# cyc_v_som_B.net
KiCad netlist of a schematic drawn in Altium Designer
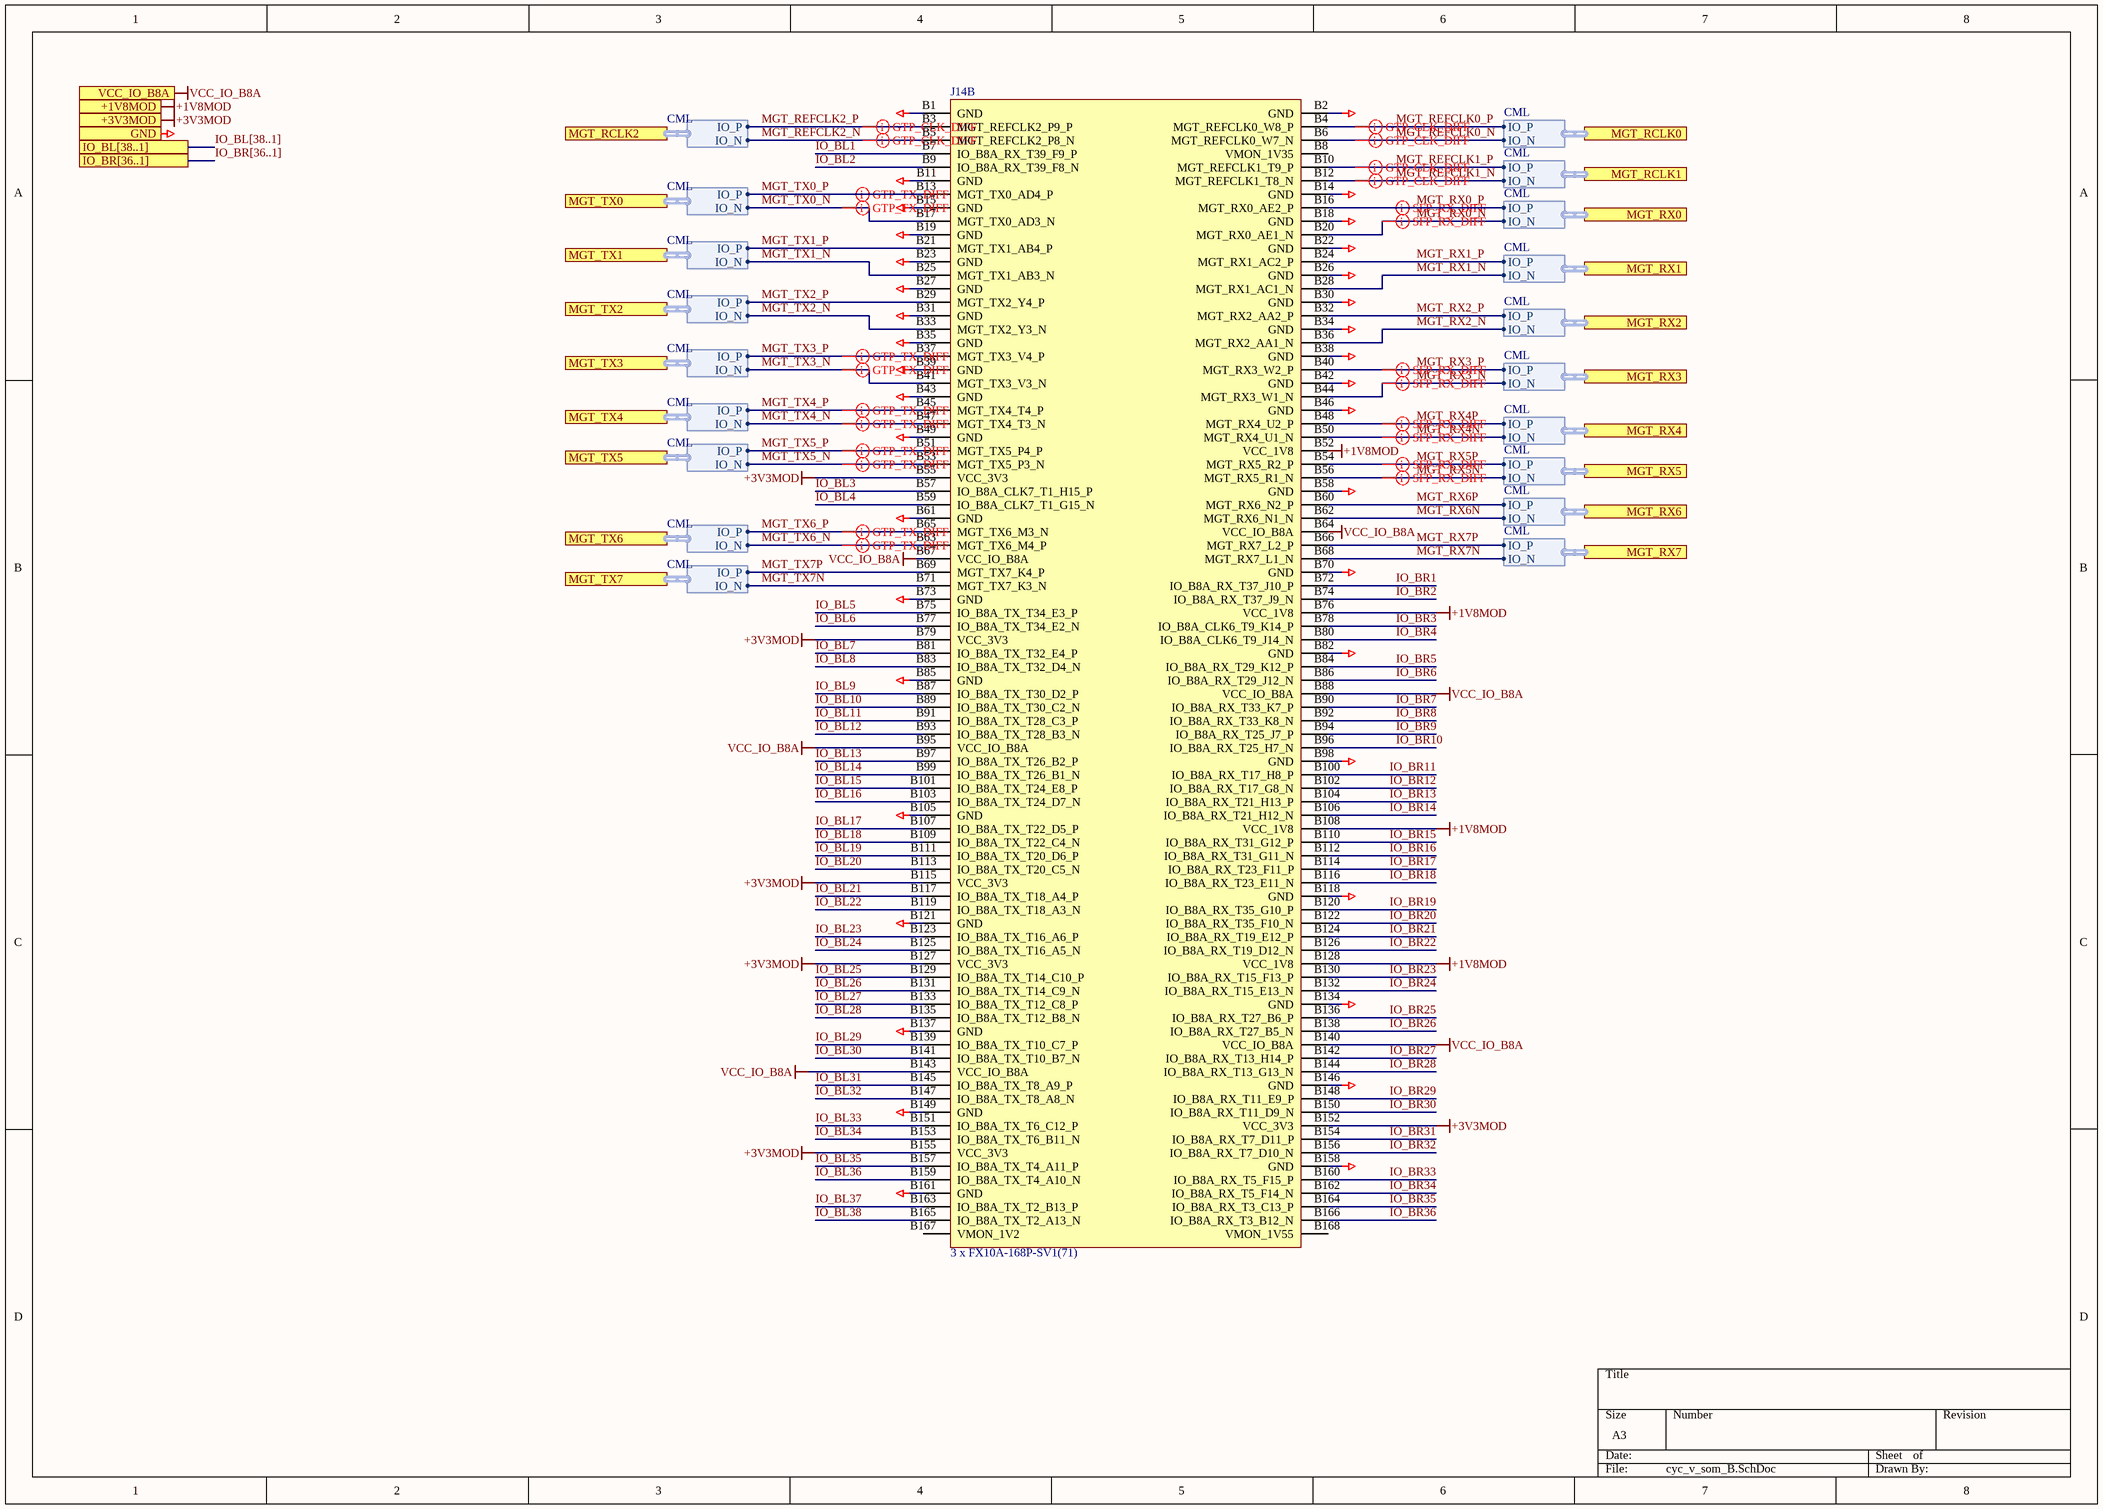
[diagram p0: cyc_v_som_B.SchDoc]

(export (version "E")
  (design (tool "Eeschema 10.0.6"))
  (components
    (comp (ref "J14")
      (value "3 x FX10A-168P-SV1(71)")
      (footprint "Mercury_SA2p")
      (libsource (lib "ConLib") (part "FX10A-168P-SV_ME-SA2+"))
    )
  )
  (nets
    (net (code "2") (name "+1V8MOD") (class "Default")
      (node (ref "J14") (pin "B108") (pinfunction "VCC_1V8_B108") (pintype "passive"))
      (node (ref "J14") (pin "B128") (pinfunction "VCC_1V8_B128") (pintype "passive"))
      (node (ref "J14") (pin "B52") (pinfunction "VCC_1V8_B52") (pintype "passive"))
      (node (ref "J14") (pin "B76") (pinfunction "VCC_1V8_B76") (pintype "passive"))
    )
    (net (code "3") (name "+3V3MOD") (class "Default")
      (node (ref "J14") (pin "B115") (pinfunction "VCC_3V3_B115") (pintype "passive"))
      (node (ref "J14") (pin "B127") (pinfunction "VCC_3V3_B127") (pintype "passive"))
      (node (ref "J14") (pin "B152") (pinfunction "VCC_3V3_B152") (pintype "passive"))
      (node (ref "J14") (pin "B155") (pinfunction "VCC_3V3_B155") (pintype "passive"))
      (node (ref "J14") (pin "B55") (pinfunction "VCC_3V3_B55") (pintype "passive"))
      (node (ref "J14") (pin "B79") (pinfunction "VCC_3V3_B79") (pintype "passive"))
    )
    (net (code "4") (name "/IO_BL1") (class "Default")
      (node (ref "J14") (pin "B7") (pinfunction "IO_B8A_RX_T39_F9_P_B7") (pintype "passive"))
    )
    (net (code "5") (name "/IO_BL2") (class "Default")
      (node (ref "J14") (pin "B9") (pinfunction "IO_B8A_RX_T39_F8_N_B9") (pintype "passive"))
    )
    (net (code "6") (name "/IO_BL3") (class "Default")
      (node (ref "J14") (pin "B57") (pinfunction "IO_B8A_CLK7_T1_H15_P_B57") (pintype "passive"))
    )
    (net (code "7") (name "/IO_BL4") (class "Default")
      (node (ref "J14") (pin "B59") (pinfunction "IO_B8A_CLK7_T1_G15_N_B59") (pintype "passive"))
    )
    (net (code "8") (name "/IO_BL5") (class "Default")
      (node (ref "J14") (pin "B75") (pinfunction "IO_B8A_TX_T34_E3_P_B75") (pintype "passive"))
    )
    (net (code "9") (name "/IO_BL6") (class "Default")
      (node (ref "J14") (pin "B77") (pinfunction "IO_B8A_TX_T34_E2_N_B77") (pintype "passive"))
    )
    (net (code "10") (name "/IO_BL7") (class "Default")
      (node (ref "J14") (pin "B81") (pinfunction "IO_B8A_TX_T32_E4_P_B81") (pintype "passive"))
    )
    (net (code "11") (name "/IO_BL8") (class "Default")
      (node (ref "J14") (pin "B83") (pinfunction "IO_B8A_TX_T32_D4_N_B83") (pintype "passive"))
    )
    (net (code "12") (name "/IO_BL9") (class "Default")
      (node (ref "J14") (pin "B87") (pinfunction "IO_B8A_TX_T30_D2_P_B87") (pintype "passive"))
    )
    (net (code "13") (name "/IO_BL10") (class "Default")
      (node (ref "J14") (pin "B89") (pinfunction "IO_B8A_TX_T30_C2_N_B89") (pintype "passive"))
    )
    (net (code "14") (name "/IO_BL11") (class "Default")
      (node (ref "J14") (pin "B91") (pinfunction "IO_B8A_TX_T28_C3_P_B91") (pintype "passive"))
    )
    (net (code "15") (name "/IO_BL12") (class "Default")
      (node (ref "J14") (pin "B93") (pinfunction "IO_B8A_TX_T28_B3_N_B93") (pintype "passive"))
    )
    (net (code "16") (name "/IO_BL13") (class "Default")
      (node (ref "J14") (pin "B97") (pinfunction "IO_B8A_TX_T26_B2_P_B97") (pintype "passive"))
    )
    (net (code "17") (name "/IO_BL14") (class "Default")
      (node (ref "J14") (pin "B99") (pinfunction "IO_B8A_TX_T26_B1_N_B99") (pintype "passive"))
    )
    (net (code "18") (name "/IO_BL15") (class "Default")
      (node (ref "J14") (pin "B101") (pinfunction "IO_B8A_TX_T24_E8_P_B101") (pintype "passive"))
    )
    (net (code "19") (name "/IO_BL16") (class "Default")
      (node (ref "J14") (pin "B103") (pinfunction "IO_B8A_TX_T24_D7_N_B103") (pintype "passive"))
    )
    (net (code "20") (name "/IO_BL17") (class "Default")
      (node (ref "J14") (pin "B107") (pinfunction "IO_B8A_TX_T22_D5_P_B107") (pintype "passive"))
    )
    (net (code "21") (name "/IO_BL18") (class "Default")
      (node (ref "J14") (pin "B109") (pinfunction "IO_B8A_TX_T22_C4_N_B109") (pintype "passive"))
    )
    (net (code "22") (name "/IO_BL19") (class "Default")
      (node (ref "J14") (pin "B111") (pinfunction "IO_B8A_TX_T20_D6_P_B111") (pintype "passive"))
    )
    (net (code "23") (name "/IO_BL20") (class "Default")
      (node (ref "J14") (pin "B113") (pinfunction "IO_B8A_TX_T20_C5_N_B113") (pintype "passive"))
    )
    (net (code "24") (name "/IO_BL21") (class "Default")
      (node (ref "J14") (pin "B117") (pinfunction "IO_B8A_TX_T18_A4_P_B117") (pintype "passive"))
    )
    (net (code "25") (name "/IO_BL22") (class "Default")
      (node (ref "J14") (pin "B119") (pinfunction "IO_B8A_TX_T18_A3_N_B119") (pintype "passive"))
    )
    (net (code "26") (name "/IO_BL23") (class "Default")
      (node (ref "J14") (pin "B123") (pinfunction "IO_B8A_TX_T16_A6_P_B123") (pintype "passive"))
    )
    (net (code "27") (name "/IO_BL24") (class "Default")
      (node (ref "J14") (pin "B125") (pinfunction "IO_B8A_TX_T16_A5_N_B125") (pintype "passive"))
    )
    (net (code "28") (name "/IO_BL25") (class "Default")
      (node (ref "J14") (pin "B129") (pinfunction "IO_B8A_TX_T14_C10_P_B129") (pintype "passive"))
    )
    (net (code "29") (name "/IO_BL26") (class "Default")
      (node (ref "J14") (pin "B131") (pinfunction "IO_B8A_TX_T14_C9_N_B131") (pintype "passive"))
    )
    (net (code "30") (name "/IO_BL27") (class "Default")
      (node (ref "J14") (pin "B133") (pinfunction "IO_B8A_TX_T12_C8_P_B133") (pintype "passive"))
    )
    (net (code "31") (name "/IO_BL28") (class "Default")
      (node (ref "J14") (pin "B135") (pinfunction "IO_B8A_TX_T12_B8_N_B135") (pintype "passive"))
    )
    (net (code "32") (name "/IO_BL29") (class "Default")
      (node (ref "J14") (pin "B139") (pinfunction "IO_B8A_TX_T10_C7_P_B139") (pintype "passive"))
    )
    (net (code "33") (name "/IO_BL30") (class "Default")
      (node (ref "J14") (pin "B141") (pinfunction "IO_B8A_TX_T10_B7_N_B141") (pintype "passive"))
    )
    (net (code "34") (name "/IO_BL31") (class "Default")
      (node (ref "J14") (pin "B145") (pinfunction "IO_B8A_TX_T8_A9_P_B145") (pintype "passive"))
    )
    (net (code "35") (name "/IO_BL32") (class "Default")
      (node (ref "J14") (pin "B147") (pinfunction "IO_B8A_TX_T8_A8_N_B147") (pintype "passive"))
    )
    (net (code "36") (name "/IO_BL33") (class "Default")
      (node (ref "J14") (pin "B151") (pinfunction "IO_B8A_TX_T6_C12_P_B151") (pintype "passive"))
    )
    (net (code "37") (name "/IO_BL34") (class "Default")
      (node (ref "J14") (pin "B153") (pinfunction "IO_B8A_TX_T6_B11_N_B153") (pintype "passive"))
    )
    (net (code "38") (name "/IO_BL35") (class "Default")
      (node (ref "J14") (pin "B157") (pinfunction "IO_B8A_TX_T4_A11_P_B157") (pintype "passive"))
    )
    (net (code "39") (name "/IO_BL36") (class "Default")
      (node (ref "J14") (pin "B159") (pinfunction "IO_B8A_TX_T4_A10_N_B159") (pintype "passive"))
    )
    (net (code "40") (name "/IO_BL37") (class "Default")
      (node (ref "J14") (pin "B163") (pinfunction "IO_B8A_TX_T2_B13_P_B163") (pintype "passive"))
    )
    (net (code "41") (name "/IO_BL38") (class "Default")
      (node (ref "J14") (pin "B165") (pinfunction "IO_B8A_TX_T2_A13_N_B165") (pintype "passive"))
    )
    (net (code "43") (name "/IO_BR1") (class "Default")
      (node (ref "J14") (pin "B72") (pinfunction "IO_B8A_RX_T37_J10_P_B72") (pintype "passive"))
    )
    (net (code "44") (name "/IO_BR2") (class "Default")
      (node (ref "J14") (pin "B74") (pinfunction "IO_B8A_RX_T37_J9_N_B74") (pintype "passive"))
    )
    (net (code "45") (name "/IO_BR3") (class "Default")
      (node (ref "J14") (pin "B78") (pinfunction "IO_B8A_CLK6_T9_K14_P_B78") (pintype "passive"))
    )
    (net (code "46") (name "/IO_BR4") (class "Default")
      (node (ref "J14") (pin "B80") (pinfunction "IO_B8A_CLK6_T9_J14_N_B80") (pintype "passive"))
    )
    (net (code "47") (name "/IO_BR5") (class "Default")
      (node (ref "J14") (pin "B84") (pinfunction "IO_B8A_RX_T29_K12_P_B84") (pintype "passive"))
    )
    (net (code "48") (name "/IO_BR6") (class "Default")
      (node (ref "J14") (pin "B86") (pinfunction "IO_B8A_RX_T29_J12_N_B86") (pintype "passive"))
    )
    (net (code "49") (name "/IO_BR7") (class "Default")
      (node (ref "J14") (pin "B90") (pinfunction "IO_B8A_RX_T33_K7_P_B90") (pintype "passive"))
    )
    (net (code "50") (name "/IO_BR8") (class "Default")
      (node (ref "J14") (pin "B92") (pinfunction "IO_B8A_RX_T33_K8_N_B92") (pintype "passive"))
    )
    (net (code "51") (name "/IO_BR9") (class "Default")
      (node (ref "J14") (pin "B94") (pinfunction "IO_B8A_RX_T25_J7_P_B94") (pintype "passive"))
    )
    (net (code "52") (name "/IO_BR10") (class "Default")
      (node (ref "J14") (pin "B96") (pinfunction "IO_B8A_RX_T25_H7_N_B96") (pintype "passive"))
    )
    (net (code "53") (name "/IO_BR11") (class "Default")
      (node (ref "J14") (pin "B100") (pinfunction "IO_B8A_RX_T17_H8_P_B100") (pintype "passive"))
    )
    (net (code "54") (name "/IO_BR12") (class "Default")
      (node (ref "J14") (pin "B102") (pinfunction "IO_B8A_RX_T17_G8_N_B102") (pintype "passive"))
    )
    (net (code "55") (name "/IO_BR13") (class "Default")
      (node (ref "J14") (pin "B104") (pinfunction "IO_B8A_RX_T21_H13_P_B104") (pintype "passive"))
    )
    (net (code "56") (name "/IO_BR14") (class "Default")
      (node (ref "J14") (pin "B106") (pinfunction "IO_B8A_RX_T21_H12_N_B106") (pintype "passive"))
    )
    (net (code "57") (name "/IO_BR15") (class "Default")
      (node (ref "J14") (pin "B110") (pinfunction "IO_B8A_RX_T31_G12_P_B110") (pintype "passive"))
    )
    (net (code "58") (name "/IO_BR16") (class "Default")
      (node (ref "J14") (pin "B112") (pinfunction "IO_B8A_RX_T31_G11_N_B112") (pintype "passive"))
    )
    (net (code "59") (name "/IO_BR17") (class "Default")
      (node (ref "J14") (pin "B114") (pinfunction "IO_B8A_RX_T23_F11_P_B114") (pintype "passive"))
    )
    (net (code "60") (name "/IO_BR18") (class "Default")
      (node (ref "J14") (pin "B116") (pinfunction "IO_B8A_RX_T23_E11_N_B116") (pintype "passive"))
    )
    (net (code "61") (name "/IO_BR19") (class "Default")
      (node (ref "J14") (pin "B120") (pinfunction "IO_B8A_RX_T35_G10_P_B120") (pintype "passive"))
    )
    (net (code "62") (name "/IO_BR20") (class "Default")
      (node (ref "J14") (pin "B122") (pinfunction "IO_B8A_RX_T35_F10_N_B122") (pintype "passive"))
    )
    (net (code "63") (name "/IO_BR21") (class "Default")
      (node (ref "J14") (pin "B124") (pinfunction "IO_B8A_RX_T19_E12_P_B124") (pintype "passive"))
    )
    (net (code "64") (name "/IO_BR22") (class "Default")
      (node (ref "J14") (pin "B126") (pinfunction "IO_B8A_RX_T19_D12_N_B126") (pintype "passive"))
    )
    (net (code "65") (name "/IO_BR23") (class "Default")
      (node (ref "J14") (pin "B130") (pinfunction "IO_B8A_RX_T15_F13_P_B130") (pintype "passive"))
    )
    (net (code "66") (name "/IO_BR24") (class "Default")
      (node (ref "J14") (pin "B132") (pinfunction "IO_B8A_RX_T15_E13_N_B132") (pintype "passive"))
    )
    (net (code "67") (name "/IO_BR25") (class "Default")
      (node (ref "J14") (pin "B136") (pinfunction "IO_B8A_RX_T27_B6_P_B136") (pintype "passive"))
    )
    (net (code "68") (name "/IO_BR26") (class "Default")
      (node (ref "J14") (pin "B138") (pinfunction "IO_B8A_RX_T27_B5_N_B138") (pintype "passive"))
    )
    (net (code "69") (name "/IO_BR27") (class "Default")
      (node (ref "J14") (pin "B142") (pinfunction "IO_B8A_RX_T13_H14_P_B142") (pintype "passive"))
    )
    (net (code "70") (name "/IO_BR28") (class "Default")
      (node (ref "J14") (pin "B144") (pinfunction "IO_B8A_RX_T13_G13_N_B144") (pintype "passive"))
    )
    (net (code "71") (name "/IO_BR29") (class "Default")
      (node (ref "J14") (pin "B148") (pinfunction "IO_B8A_RX_T11_E9_P_B148") (pintype "passive"))
    )
    (net (code "72") (name "/IO_BR30") (class "Default")
      (node (ref "J14") (pin "B150") (pinfunction "IO_B8A_RX_T11_D9_N_B150") (pintype "passive"))
    )
    (net (code "73") (name "/IO_BR31") (class "Default")
      (node (ref "J14") (pin "B154") (pinfunction "IO_B8A_RX_T7_D11_P_B154") (pintype "passive"))
    )
    (net (code "74") (name "/IO_BR32") (class "Default")
      (node (ref "J14") (pin "B156") (pinfunction "IO_B8A_RX_T7_D10_N_B156") (pintype "passive"))
    )
    (net (code "75") (name "/IO_BR33") (class "Default")
      (node (ref "J14") (pin "B160") (pinfunction "IO_B8A_RX_T5_F15_P_B160") (pintype "passive"))
    )
    (net (code "76") (name "/IO_BR34") (class "Default")
      (node (ref "J14") (pin "B162") (pinfunction "IO_B8A_RX_T5_F14_N_B162") (pintype "passive"))
    )
    (net (code "77") (name "/IO_BR35") (class "Default")
      (node (ref "J14") (pin "B164") (pinfunction "IO_B8A_RX_T3_C13_P_B164") (pintype "passive"))
    )
    (net (code "78") (name "/IO_BR36") (class "Default")
      (node (ref "J14") (pin "B166") (pinfunction "IO_B8A_RX_T3_B12_N_B166") (pintype "passive"))
    )
    (net (code "80") (name "/MGT_REFCLK0_N") (class "Default")
      (node (ref "J14") (pin "B6") (pinfunction "MGT_REFCLK0_W7_N_B6") (pintype "passive"))
    )
    (net (code "81") (name "/MGT_REFCLK0_P") (class "Default")
      (node (ref "J14") (pin "B4") (pinfunction "MGT_REFCLK0_W8_P_B4") (pintype "passive"))
    )
    (net (code "82") (name "/MGT_REFCLK1_N") (class "Default")
      (node (ref "J14") (pin "B12") (pinfunction "MGT_REFCLK1_T8_N_B12") (pintype "passive"))
    )
    (net (code "83") (name "/MGT_REFCLK1_P") (class "Default")
      (node (ref "J14") (pin "B10") (pinfunction "MGT_REFCLK1_T9_P_B10") (pintype "passive"))
    )
    (net (code "84") (name "/MGT_REFCLK2_N") (class "Default")
      (node (ref "J14") (pin "B5") (pinfunction "MGT_REFCLK2_P8_N_B5") (pintype "passive"))
    )
    (net (code "85") (name "/MGT_REFCLK2_P") (class "Default")
      (node (ref "J14") (pin "B3") (pinfunction "MGT_REFCLK2_P9_P_B3") (pintype "passive"))
    )
    (net (code "86") (name "/MGT_RX0_N") (class "Default")
      (node (ref "J14") (pin "B20") (pinfunction "MGT_RX0_AE1_N_B20") (pintype "passive"))
    )
    (net (code "87") (name "/MGT_RX0_P") (class "Default")
      (node (ref "J14") (pin "B16") (pinfunction "MGT_RX0_AE2_P_B16") (pintype "passive"))
    )
    (net (code "88") (name "/MGT_RX1_N") (class "Default")
      (node (ref "J14") (pin "B28") (pinfunction "MGT_RX1_AC1_N_B28") (pintype "passive"))
    )
    (net (code "89") (name "/MGT_RX1_P") (class "Default")
      (node (ref "J14") (pin "B24") (pinfunction "MGT_RX1_AC2_P_B24") (pintype "passive"))
    )
    (net (code "90") (name "/MGT_RX2_N") (class "Default")
      (node (ref "J14") (pin "B36") (pinfunction "MGT_RX2_AA1_N_B36") (pintype "passive"))
    )
    (net (code "91") (name "/MGT_RX2_P") (class "Default")
      (node (ref "J14") (pin "B32") (pinfunction "MGT_RX2_AA2_P_B32") (pintype "passive"))
    )
    (net (code "92") (name "/MGT_RX3_N") (class "Default")
      (node (ref "J14") (pin "B44") (pinfunction "MGT_RX3_W1_N_B44") (pintype "passive"))
    )
    (net (code "93") (name "/MGT_RX3_P") (class "Default")
      (node (ref "J14") (pin "B40") (pinfunction "MGT_RX3_W2_P_B40") (pintype "passive"))
    )
    (net (code "94") (name "/MGT_RX4N") (class "Default")
      (node (ref "J14") (pin "B50") (pinfunction "MGT_RX4_U1_N_B50") (pintype "passive"))
    )
    (net (code "95") (name "/MGT_RX4P") (class "Default")
      (node (ref "J14") (pin "B48") (pinfunction "MGT_RX4_U2_P_B48") (pintype "passive"))
    )
    (net (code "96") (name "/MGT_RX5N") (class "Default")
      (node (ref "J14") (pin "B56") (pinfunction "MGT_RX5_R1_N_B56") (pintype "passive"))
    )
    (net (code "97") (name "/MGT_RX5P") (class "Default")
      (node (ref "J14") (pin "B54") (pinfunction "MGT_RX5_R2_P_B54") (pintype "passive"))
    )
    (net (code "98") (name "/MGT_RX6N") (class "Default")
      (node (ref "J14") (pin "B62") (pinfunction "MGT_RX6_N1_N_B62") (pintype "passive"))
    )
    (net (code "99") (name "/MGT_RX6P") (class "Default")
      (node (ref "J14") (pin "B60") (pinfunction "MGT_RX6_N2_P_B60") (pintype "passive"))
    )
    (net (code "100") (name "/MGT_RX7N") (class "Default")
      (node (ref "J14") (pin "B68") (pinfunction "MGT_RX7_L1_N_B68") (pintype "passive"))
    )
    (net (code "101") (name "/MGT_RX7P") (class "Default")
      (node (ref "J14") (pin "B66") (pinfunction "MGT_RX7_L2_P_B66") (pintype "passive"))
    )
    (net (code "102") (name "/MGT_TX0_N") (class "Default")
      (node (ref "J14") (pin "B17") (pinfunction "MGT_TX0_AD3_N_B17") (pintype "passive"))
    )
    (net (code "103") (name "/MGT_TX0_P") (class "Default")
      (node (ref "J14") (pin "B13") (pinfunction "MGT_TX0_AD4_P_B13") (pintype "passive"))
    )
    (net (code "104") (name "/MGT_TX1_N") (class "Default")
      (node (ref "J14") (pin "B25") (pinfunction "MGT_TX1_AB3_N_B25") (pintype "passive"))
    )
    (net (code "105") (name "/MGT_TX1_P") (class "Default")
      (node (ref "J14") (pin "B21") (pinfunction "MGT_TX1_AB4_P_B21") (pintype "passive"))
    )
    (net (code "106") (name "/MGT_TX2_N") (class "Default")
      (node (ref "J14") (pin "B33") (pinfunction "MGT_TX2_Y3_N_B33") (pintype "passive"))
    )
    (net (code "107") (name "/MGT_TX2_P") (class "Default")
      (node (ref "J14") (pin "B29") (pinfunction "MGT_TX2_Y4_P_B29") (pintype "passive"))
    )
    (net (code "108") (name "/MGT_TX3_N") (class "Default")
      (node (ref "J14") (pin "B41") (pinfunction "MGT_TX3_V3_N_B41") (pintype "passive"))
    )
    (net (code "109") (name "/MGT_TX3_P") (class "Default")
      (node (ref "J14") (pin "B37") (pinfunction "MGT_TX3_V4_P_B37") (pintype "passive"))
    )
    (net (code "110") (name "/MGT_TX4_N") (class "Default")
      (node (ref "J14") (pin "B47") (pinfunction "MGT_TX4_T3_N_B47") (pintype "passive"))
    )
    (net (code "111") (name "/MGT_TX4_P") (class "Default")
      (node (ref "J14") (pin "B45") (pinfunction "MGT_TX4_T4_P_B45") (pintype "passive"))
    )
    (net (code "112") (name "/MGT_TX5_N") (class "Default")
      (node (ref "J14") (pin "B53") (pinfunction "MGT_TX5_P3_N_B53") (pintype "passive"))
    )
    (net (code "113") (name "/MGT_TX5_P") (class "Default")
      (node (ref "J14") (pin "B51") (pinfunction "MGT_TX5_P4_P_B51") (pintype "passive"))
    )
    (net (code "114") (name "/MGT_TX6_N") (class "Default")
      (node (ref "J14") (pin "B63") (pinfunction "MGT_TX6_M4_P_B63") (pintype "passive"))
    )
    (net (code "115") (name "/MGT_TX6_P") (class "Default")
      (node (ref "J14") (pin "B65") (pinfunction "MGT_TX6_M3_N_B65") (pintype "passive"))
    )
    (net (code "116") (name "/MGT_TX7N") (class "Default")
      (node (ref "J14") (pin "B71") (pinfunction "MGT_TX7_K3_N_B71") (pintype "passive"))
    )
    (net (code "117") (name "/MGT_TX7P") (class "Default")
      (node (ref "J14") (pin "B69") (pinfunction "MGT_TX7_K4_P_B69") (pintype "passive"))
    )
    (net (code "119") (name "GND") (class "Default")
      (node (ref "J14") (pin "B1") (pinfunction "GND_B1") (pintype "passive"))
      (node (ref "J14") (pin "B105") (pinfunction "GND_B105") (pintype "passive"))
      (node (ref "J14") (pin "B11") (pinfunction "GND_B11") (pintype "passive"))
      (node (ref "J14") (pin "B118") (pinfunction "GND_B118") (pintype "passive"))
      (node (ref "J14") (pin "B121") (pinfunction "GND_B121") (pintype "passive"))
      (node (ref "J14") (pin "B134") (pinfunction "GND_B134") (pintype "passive"))
      (node (ref "J14") (pin "B137") (pinfunction "GND_B137") (pintype "passive"))
      (node (ref "J14") (pin "B14") (pinfunction "GND_B14") (pintype "passive"))
      (node (ref "J14") (pin "B146") (pinfunction "GND_B146") (pintype "passive"))
      (node (ref "J14") (pin "B149") (pinfunction "GND_B149") (pintype "passive"))
      (node (ref "J14") (pin "B15") (pinfunction "GND_B15") (pintype "passive"))
      (node (ref "J14") (pin "B158") (pinfunction "GND_B158") (pintype "passive"))
      (node (ref "J14") (pin "B161") (pinfunction "GND_B161") (pintype "passive"))
      (node (ref "J14") (pin "B18") (pinfunction "GND_B18") (pintype "passive"))
      (node (ref "J14") (pin "B19") (pinfunction "GND_B19") (pintype "passive"))
      (node (ref "J14") (pin "B2") (pinfunction "GND_B2") (pintype "passive"))
      (node (ref "J14") (pin "B22") (pinfunction "GND_B22") (pintype "passive"))
      (node (ref "J14") (pin "B23") (pinfunction "GND_B23") (pintype "passive"))
      (node (ref "J14") (pin "B26") (pinfunction "GND_B26") (pintype "passive"))
      (node (ref "J14") (pin "B27") (pinfunction "GND_B27") (pintype "passive"))
      (node (ref "J14") (pin "B30") (pinfunction "GND_B30") (pintype "passive"))
      (node (ref "J14") (pin "B31") (pinfunction "GND_B31") (pintype "passive"))
      (node (ref "J14") (pin "B34") (pinfunction "GND_B34") (pintype "passive"))
      (node (ref "J14") (pin "B35") (pinfunction "GND_B35") (pintype "passive"))
      (node (ref "J14") (pin "B38") (pinfunction "GND_B38") (pintype "passive"))
      (node (ref "J14") (pin "B39") (pinfunction "GND_B39") (pintype "passive"))
      (node (ref "J14") (pin "B42") (pinfunction "GND_B42") (pintype "passive"))
      (node (ref "J14") (pin "B43") (pinfunction "GND_B43") (pintype "passive"))
      (node (ref "J14") (pin "B46") (pinfunction "GND_B46") (pintype "passive"))
      (node (ref "J14") (pin "B49") (pinfunction "GND_B49") (pintype "passive"))
      (node (ref "J14") (pin "B58") (pinfunction "GND_B58") (pintype "passive"))
      (node (ref "J14") (pin "B61") (pinfunction "GND_B61") (pintype "passive"))
      (node (ref "J14") (pin "B70") (pinfunction "GND_B70") (pintype "passive"))
      (node (ref "J14") (pin "B73") (pinfunction "GND_B73") (pintype "passive"))
      (node (ref "J14") (pin "B82") (pinfunction "GND_B82") (pintype "passive"))
      (node (ref "J14") (pin "B85") (pinfunction "GND_B85") (pintype "passive"))
      (node (ref "J14") (pin "B98") (pinfunction "GND_B98") (pintype "passive"))
    )
    (net (code "120") (name "VCC_IO_B8A") (class "Default")
      (node (ref "J14") (pin "B140") (pinfunction "VCC_IO_B8A_B140") (pintype "passive"))
      (node (ref "J14") (pin "B143") (pinfunction "VCC_IO_B8A_B143") (pintype "passive"))
      (node (ref "J14") (pin "B64") (pinfunction "VCC_IO_B8A_B64") (pintype "passive"))
      (node (ref "J14") (pin "B67") (pinfunction "VCC_IO_B8A_B67") (pintype "passive"))
      (node (ref "J14") (pin "B88") (pinfunction "VCC_IO_B8A_B88") (pintype "passive"))
      (node (ref "J14") (pin "B95") (pinfunction "VCC_IO_B8A_B95") (pintype "passive"))
    )
    (net (code "121") (name "unconnected-(J14B-VMON_1V2-PadB167)") (class "Default")
      (node (ref "J14") (pin "B167") (pinfunction "VMON_1V2_B167") (pintype "passive"))
    )
    (net (code "122") (name "unconnected-(J14B-VMON_1V35-PadB8)") (class "Default")
      (node (ref "J14") (pin "B8") (pinfunction "VMON_1V35_B8") (pintype "passive"))
    )
    (net (code "123") (name "unconnected-(J14B-VMON_1V55-PadB168)") (class "Default")
      (node (ref "J14") (pin "B168") (pinfunction "VMON_1V55_B168") (pintype "passive"))
    )
  )
)
